# Thermocouple.net
KiCad netlist of a schematic drawn in Altium Designer
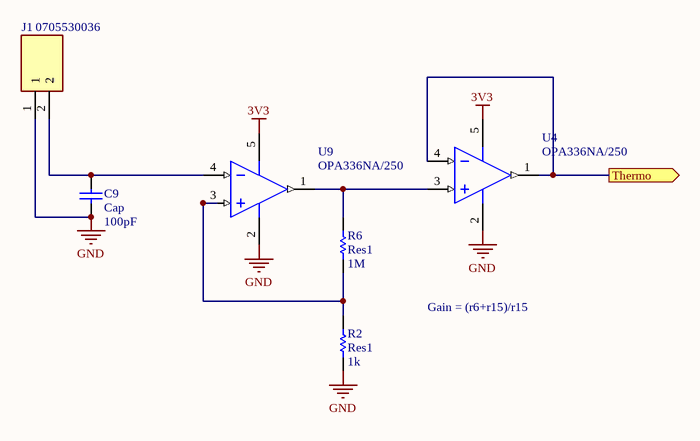
[diagram p0: Thermocouple.SchDoc]

(export (version "E")
  (design (tool "Eeschema 10.0.6"))
  (components
    (comp (ref "C9")
      (value "Cap")
      (footprint "0402-A")
      (description "Capacitor")
      (fields (field (name "ALTIUM_VALUE") "100pF") (field (name "PUBLISHER") "Altium Limited"))
      (libsource (lib "Miscellaneous Devices") (part "Cap"))
    )
    (comp (ref "J1")
      (value "0705530036")
      (footprint "SamacSys:SHDRRA2W64P0X254_1X2_737X1359X699P")
      (description "Connector")
      (libsource (lib "*") (part "0705530036"))
    )
    (comp (ref "R2")
      (value "Res1")
      (footprint "0402-A")
      (description "Resistor")
      (fields (field (name "ALTIUM_VALUE") "1k") (field (name "PUBLISHER") "Altium Limited"))
      (libsource (lib "Miscellaneous Devices") (part "Res1"))
    )
    (comp (ref "R6")
      (value "Res1")
      (footprint "0402-A")
      (description "Resistor")
      (fields (field (name "ALTIUM_VALUE") "1M") (field (name "PUBLISHER") "Altium Limited"))
      (libsource (lib "Miscellaneous Devices") (part "Res1"))
    )
    (comp (ref "U4")
      (value "OPA336NA/250")
      (footprint "DBV0005A_M")
      (fields (field (name "MANUFACTURER") "Texas Instruments"))
      (libsource (lib "Altium Content Vault") (part "TI-OPA_SM7XXXX-DBV5"))
    )
    (comp (ref "U9")
      (value "OPA336NA/250")
      (footprint "DBV0005A_M")
      (fields (field (name "MANUFACTURER") "Texas Instruments"))
      (libsource (lib "Altium Content Vault") (part "TI-OPA_SM7XXXX-DBV5"))
    )
  )
  (nets
    (net (code "1") (name "/Thermo") (class "Default")
      (node (ref "U4") (pin "1") (pinfunction "OUT_1") (pintype "output"))
      (node (ref "U4") (pin "4") (pinfunction "IN-_4") (pintype "input"))
    )
    (net (code "2") (name "3V3") (class "Default")
      (node (ref "U4") (pin "5") (pinfunction "V+_5") (pintype "power_in"))
      (node (ref "U9") (pin "5") (pinfunction "V+_5") (pintype "power_in"))
    )
    (net (code "3") (name "GND") (class "Default")
      (node (ref "C9") (pin "1") (pinfunction "1_1") (pintype "passive"))
      (node (ref "J1") (pin "1") (pinfunction "1_1") (pintype "passive"))
      (node (ref "R2") (pin "2") (pinfunction "2_2") (pintype "passive"))
      (node (ref "U4") (pin "2") (pinfunction "V-_2") (pintype "power_in"))
      (node (ref "U9") (pin "2") (pinfunction "V-_2") (pintype "power_in"))
    )
    (net (code "4") (name "Net-(U4-IN+)") (class "Default")
      (node (ref "R6") (pin "1") (pinfunction "1_1") (pintype "passive"))
      (node (ref "U4") (pin "3") (pinfunction "IN+_3") (pintype "input"))
      (node (ref "U9") (pin "1") (pinfunction "OUT_1") (pintype "output"))
    )
    (net (code "5") (name "Net-(U9-IN+)") (class "Default")
      (node (ref "R2") (pin "1") (pinfunction "1_1") (pintype "passive"))
      (node (ref "R6") (pin "2") (pinfunction "2_2") (pintype "passive"))
      (node (ref "U9") (pin "3") (pinfunction "IN+_3") (pintype "input"))
    )
    (net (code "6") (name "Net-(U9-IN-)") (class "Default")
      (node (ref "C9") (pin "2") (pinfunction "2_2") (pintype "passive"))
      (node (ref "J1") (pin "2") (pinfunction "2_2") (pintype "passive"))
      (node (ref "U9") (pin "4") (pinfunction "IN-_4") (pintype "input"))
    )
  )
)
